# motorEncoder.net
KiCad netlist of a schematic drawn in Altium Designer
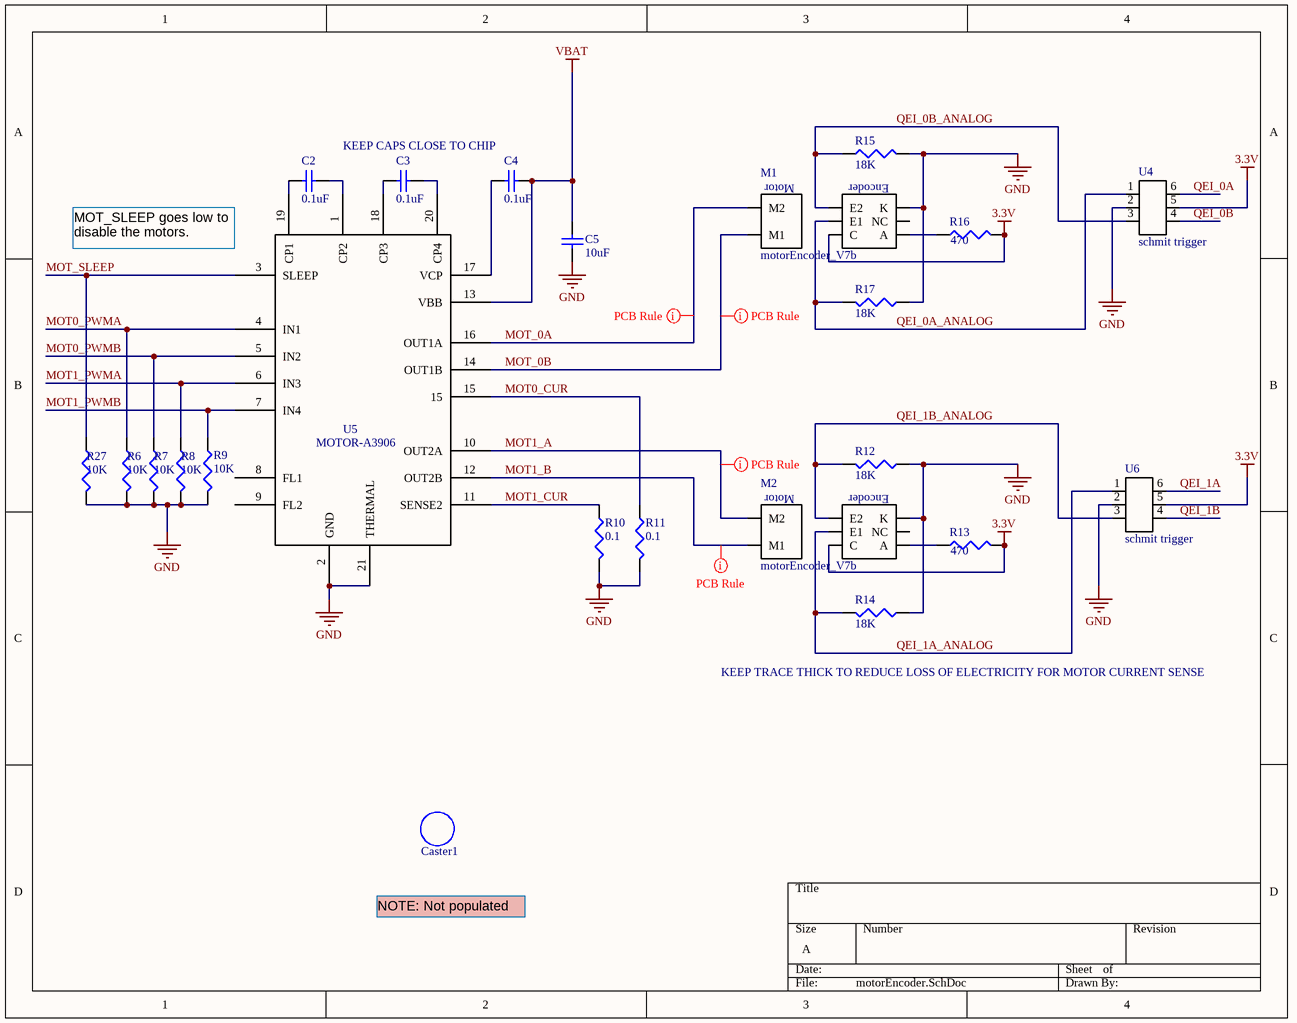
[diagram p0: motorEncoder.SchDoc]

(export (version "E")
  (design (tool "Eeschema 10.0.6"))
  (components
    (comp (ref "C2")
      (value "0.1uF")
      (footprint "CAPC1005L")
      (description "Capacitor (Semiconductor SIM Model)")
      (fields (field (name "Comment") "Cap Semi") (field (name "PUBLISHER") "Altium Limited"))
      (libsource (lib "Miscellaneous Devices") (part "Cap Semi"))
    )
    (comp (ref "C3")
      (value "0.1uF")
      (footprint "CAPC1005L")
      (description "Capacitor (Semiconductor SIM Model)")
      (fields (field (name "Comment") "Cap Semi") (field (name "PUBLISHER") "Altium Limited"))
      (libsource (lib "Miscellaneous Devices") (part "Cap Semi"))
    )
    (comp (ref "C4")
      (value "0.1uF")
      (footprint "CAPC1005L")
      (description "Capacitor (Semiconductor SIM Model)")
      (fields (field (name "Comment") "Cap Semi") (field (name "PUBLISHER") "Altium Limited"))
      (libsource (lib "Miscellaneous Devices") (part "Cap Semi"))
    )
    (comp (ref "C5")
      (value "10uF")
      (footprint "CAPC1608L")
      (description "Capacitor (Semiconductor SIM Model)")
      (fields (field (name "Comment") "Cap Semi") (field (name "PUBLISHER") "Altium Limited"))
      (libsource (lib "Miscellaneous Devices") (part "Cap Semi"))
    )
    (comp (ref "Caster1")
      (value "non connect")
      (footprint "3/4\"CASTER2")
      (description "This is just a space saver to get the caster onto the pcb")
      (libsource (lib "mrone") (part "Caster 3/4in"))
    )
    (comp (ref "M1")
      (value "motorEncoder_V7b")
      (footprint "motorEncoder_V7b")
      (libsource (lib "mrone") (part "motorEncoder_V7b"))
    )
    (comp (ref "M2")
      (value "motorEncoder_V7b")
      (footprint "motorEncoder_V7b")
      (libsource (lib "mrone") (part "motorEncoder_V7b"))
    )
    (comp (ref "R6")
      (value "10K")
      (footprint "RESC1608L")
      (description "Resistor")
      (fields (field (name "Comment") "Res3") (field (name "PUBLISHER") "Altium Limited"))
      (libsource (lib "Miscellaneous Devices") (part "Res3"))
    )
    (comp (ref "R7")
      (value "10K")
      (footprint "RESC1608L")
      (description "Resistor")
      (fields (field (name "Comment") "Res3") (field (name "PUBLISHER") "Altium Limited"))
      (libsource (lib "Miscellaneous Devices") (part "Res3"))
    )
    (comp (ref "R8")
      (value "10K")
      (footprint "RESC1608L")
      (description "Resistor")
      (fields (field (name "Comment") "Res3") (field (name "PUBLISHER") "Altium Limited"))
      (libsource (lib "Miscellaneous Devices") (part "Res3"))
    )
    (comp (ref "R9")
      (value "10K")
      (footprint "RESC1608L")
      (description "Resistor")
      (fields (field (name "Comment") "Res3") (field (name "PUBLISHER") "Altium Limited"))
      (libsource (lib "Miscellaneous Devices") (part "Res3"))
    )
    (comp (ref "R10")
      (value "0.1")
      (footprint "RESC1608L")
      (description "Resistor")
      (fields (field (name "Comment") "Res3") (field (name "PUBLISHER") "Altium Limited"))
      (libsource (lib "Miscellaneous Devices") (part "Res3"))
    )
    (comp (ref "R11")
      (value "0.1")
      (footprint "RESC1608L")
      (description "Resistor")
      (fields (field (name "Comment") "Res3") (field (name "PUBLISHER") "Altium Limited"))
      (libsource (lib "Miscellaneous Devices") (part "Res3"))
    )
    (comp (ref "R12")
      (value "18K")
      (footprint "RESC1608L")
      (description "Resistor")
      (fields (field (name "PUBLISHER") "Altium Limited"))
      (libsource (lib "Miscellaneous Devices") (part "Res3"))
    )
    (comp (ref "R13")
      (value "470")
      (footprint "RESC1608L")
      (description "Resistor")
      (fields (field (name "PUBLISHER") "Altium Limited"))
      (libsource (lib "Miscellaneous Devices") (part "Res3"))
    )
    (comp (ref "R14")
      (value "18K")
      (footprint "RESC1608L")
      (description "Resistor")
      (fields (field (name "PUBLISHER") "Altium Limited"))
      (libsource (lib "Miscellaneous Devices") (part "Res3"))
    )
    (comp (ref "R15")
      (value "18K")
      (footprint "RESC1608L")
      (description "Resistor")
      (fields (field (name "PUBLISHER") "Altium Limited"))
      (libsource (lib "Miscellaneous Devices") (part "Res3"))
    )
    (comp (ref "R16")
      (value "470")
      (footprint "RESC1608L")
      (description "Resistor")
      (fields (field (name "PUBLISHER") "Altium Limited"))
      (libsource (lib "Miscellaneous Devices") (part "Res3"))
    )
    (comp (ref "R17")
      (value "18K")
      (footprint "RESC1608L")
      (description "Resistor")
      (fields (field (name "PUBLISHER") "Altium Limited"))
      (libsource (lib "Miscellaneous Devices") (part "Res3"))
    )
    (comp (ref "R27")
      (value "10K")
      (footprint "CAPC1608L")
      (description "Resistor")
      (fields (field (name "Comment") "Res3") (field (name "PUBLISHER") "Altium Limited"))
      (libsource (lib "Miscellaneous Devices") (part "Res3"))
    )
    (comp (ref "U4")
      (value "schmit trigger")
      (footprint "DCK(R-PDSO-C6)")
      (libsource (lib "mrone") (part "schmit trigger"))
    )
    (comp (ref "U5")
      (value "MOTOR-A3906")
      (footprint "QFN-20")
      (libsource (lib "V2_altium") (part "MOTOR-A3906"))
    )
    (comp (ref "U6")
      (value "schmit trigger")
      (footprint "DCK(R-PDSO-C6)")
      (libsource (lib "mrone") (part "schmit trigger"))
    )
  )
  (nets
    (net (code "2") (name "/MOT0_CUR") (class "Default")
      (node (ref "R11") (pin "1") (pinfunction "1_1") (pintype "passive"))
      (node (ref "U5") (pin "15") (pinfunction "15_15") (pintype "passive"))
    )
    (net (code "3") (name "/MOT0_PWMA") (class "Default")
      (node (ref "R6") (pin "1") (pinfunction "1_1") (pintype "passive"))
      (node (ref "U5") (pin "4") (pinfunction "IN1_4") (pintype "passive"))
    )
    (net (code "4") (name "/MOT0_PWMB") (class "Default")
      (node (ref "R7") (pin "1") (pinfunction "1_1") (pintype "passive"))
      (node (ref "U5") (pin "5") (pinfunction "IN2_5") (pintype "passive"))
    )
    (net (code "5") (name "/MOT1_A") (class "Default")
      (node (ref "M2") (pin "M2") (pinfunction "M2_M2") (pintype "passive"))
      (node (ref "U5") (pin "10") (pinfunction "OUT2A_10") (pintype "passive"))
    )
    (net (code "6") (name "/MOT1_B") (class "Default")
      (node (ref "M2") (pin "M1") (pinfunction "M1_M1") (pintype "passive"))
      (node (ref "U5") (pin "12") (pinfunction "OUT2B_12") (pintype "passive"))
    )
    (net (code "7") (name "/MOT1_CUR") (class "Default")
      (node (ref "R10") (pin "1") (pinfunction "1_1") (pintype "passive"))
      (node (ref "U5") (pin "11") (pinfunction "SENSE2_11") (pintype "passive"))
    )
    (net (code "8") (name "/MOT1_PWMA") (class "Default")
      (node (ref "R8") (pin "1") (pinfunction "1_1") (pintype "passive"))
      (node (ref "U5") (pin "6") (pinfunction "IN3_6") (pintype "passive"))
    )
    (net (code "9") (name "/MOT1_PWMB") (class "Default")
      (node (ref "R9") (pin "1") (pinfunction "1_1") (pintype "passive"))
      (node (ref "U5") (pin "7") (pinfunction "IN4_7") (pintype "passive"))
    )
    (net (code "10") (name "/MOT_0A") (class "Default")
      (node (ref "M1") (pin "M2") (pinfunction "M2_M2") (pintype "passive"))
      (node (ref "U5") (pin "16") (pinfunction "OUT1A_16") (pintype "passive"))
    )
    (net (code "11") (name "/MOT_0B") (class "Default")
      (node (ref "M1") (pin "M1") (pinfunction "M1_M1") (pintype "passive"))
      (node (ref "U5") (pin "14") (pinfunction "OUT1B_14") (pintype "passive"))
    )
    (net (code "12") (name "/MOT_SLEEP") (class "Default")
      (node (ref "R27") (pin "1") (pinfunction "1_1") (pintype "passive"))
      (node (ref "U5") (pin "3") (pinfunction "SLEEP_3") (pintype "passive"))
    )
    (net (code "13") (name "/QEI_0A") (class "Default")
      (node (ref "U4") (pin "6") (pinfunction "4_6") (pintype "passive"))
    )
    (net (code "14") (name "/QEI_0A_ANALOG") (class "Default")
      (node (ref "M1") (pin "E1") (pinfunction "E1_E1") (pintype "passive"))
      (node (ref "R17") (pin "2") (pinfunction "2_2") (pintype "passive"))
      (node (ref "U4") (pin "1") (pinfunction "1_1") (pintype "passive"))
    )
    (net (code "15") (name "/QEI_0B") (class "Default")
      (node (ref "U4") (pin "4") (pinfunction "4_4") (pintype "passive"))
    )
    (net (code "16") (name "/QEI_0B_ANALOG") (class "Default")
      (node (ref "M1") (pin "E2") (pinfunction "E2_E2") (pintype "passive"))
      (node (ref "R15") (pin "1") (pinfunction "1_1") (pintype "passive"))
      (node (ref "U4") (pin "3") (pinfunction "3_3") (pintype "passive"))
    )
    (net (code "17") (name "/QEI_1A") (class "Default")
      (node (ref "U6") (pin "6") (pinfunction "4_6") (pintype "passive"))
    )
    (net (code "18") (name "/QEI_1A_ANALOG") (class "Default")
      (node (ref "M2") (pin "E1") (pinfunction "E1_E1") (pintype "passive"))
      (node (ref "R14") (pin "2") (pinfunction "2_2") (pintype "passive"))
      (node (ref "U6") (pin "1") (pinfunction "1_1") (pintype "passive"))
    )
    (net (code "19") (name "/QEI_1B") (class "Default")
      (node (ref "U6") (pin "4") (pinfunction "4_4") (pintype "passive"))
    )
    (net (code "20") (name "/QEI_1B_ANALOG") (class "Default")
      (node (ref "M2") (pin "E2") (pinfunction "E2_E2") (pintype "passive"))
      (node (ref "R12") (pin "2") (pinfunction "2_2") (pintype "passive"))
      (node (ref "U6") (pin "3") (pinfunction "3_3") (pintype "passive"))
    )
    (net (code "21") (name "3.3V") (class "Default")
      (node (ref "M1") (pin "C") (pinfunction "C_C") (pintype "passive"))
      (node (ref "M2") (pin "C") (pinfunction "C_C") (pintype "passive"))
      (node (ref "R13") (pin "2") (pinfunction "2_2") (pintype "passive"))
      (node (ref "R16") (pin "2") (pinfunction "2_2") (pintype "passive"))
      (node (ref "U4") (pin "5") (pinfunction "5_5") (pintype "passive"))
      (node (ref "U6") (pin "5") (pinfunction "5_5") (pintype "passive"))
    )
    (net (code "22") (name "GND") (class "Default")
      (node (ref "C5") (pin "1") (pinfunction "1_1") (pintype "passive"))
      (node (ref "M1") (pin "K") (pinfunction "K_K") (pintype "passive"))
      (node (ref "M2") (pin "K") (pinfunction "K_K") (pintype "passive"))
      (node (ref "R10") (pin "2") (pinfunction "2_2") (pintype "passive"))
      (node (ref "R11") (pin "2") (pinfunction "2_2") (pintype "passive"))
      (node (ref "R12") (pin "1") (pinfunction "1_1") (pintype "passive"))
      (node (ref "R14") (pin "1") (pinfunction "1_1") (pintype "passive"))
      (node (ref "R15") (pin "2") (pinfunction "2_2") (pintype "passive"))
      (node (ref "R17") (pin "1") (pinfunction "1_1") (pintype "passive"))
      (node (ref "R27") (pin "2") (pinfunction "2_2") (pintype "passive"))
      (node (ref "R6") (pin "2") (pinfunction "2_2") (pintype "passive"))
      (node (ref "R7") (pin "2") (pinfunction "2_2") (pintype "passive"))
      (node (ref "R8") (pin "2") (pinfunction "2_2") (pintype "passive"))
      (node (ref "R9") (pin "2") (pinfunction "2_2") (pintype "passive"))
      (node (ref "U4") (pin "2") (pinfunction "2_2") (pintype "passive"))
      (node (ref "U5") (pin "2") (pinfunction "GND_2") (pintype "passive"))
      (node (ref "U5") (pin "21") (pinfunction "THERMAL_21") (pintype "passive"))
      (node (ref "U6") (pin "2") (pinfunction "2_2") (pintype "passive"))
    )
    (net (code "23") (name "Net-(M1-PadA)") (class "Default")
      (node (ref "M1") (pin "A") (pinfunction "A_A") (pintype "passive"))
      (node (ref "R16") (pin "1") (pinfunction "1_1") (pintype "passive"))
    )
    (net (code "24") (name "Net-(M2-PadA)") (class "Default")
      (node (ref "M2") (pin "A") (pinfunction "A_A") (pintype "passive"))
      (node (ref "R13") (pin "1") (pinfunction "1_1") (pintype "passive"))
    )
    (net (code "25") (name "Net-(U5-CP1)") (class "Default")
      (node (ref "C2") (pin "1") (pinfunction "1_1") (pintype "passive"))
      (node (ref "U5") (pin "19") (pinfunction "CP1_19") (pintype "passive"))
    )
    (net (code "26") (name "Net-(U5-CP2)") (class "Default")
      (node (ref "C2") (pin "2") (pinfunction "2_2") (pintype "passive"))
      (node (ref "U5") (pin "1") (pinfunction "CP2_1") (pintype "passive"))
    )
    (net (code "27") (name "Net-(U5-CP3)") (class "Default")
      (node (ref "C3") (pin "1") (pinfunction "1_1") (pintype "passive"))
      (node (ref "U5") (pin "18") (pinfunction "CP3_18") (pintype "passive"))
    )
    (net (code "28") (name "Net-(U5-CP4)") (class "Default")
      (node (ref "C3") (pin "2") (pinfunction "2_2") (pintype "passive"))
      (node (ref "U5") (pin "20") (pinfunction "CP4_20") (pintype "passive"))
    )
    (net (code "29") (name "Net-(U5-VCP)") (class "Default")
      (node (ref "C4") (pin "2") (pinfunction "2_2") (pintype "passive"))
      (node (ref "U5") (pin "17") (pinfunction "VCP_17") (pintype "passive"))
    )
    (net (code "30") (name "VBAT") (class "Default")
      (node (ref "C4") (pin "1") (pinfunction "1_1") (pintype "passive"))
      (node (ref "C5") (pin "2") (pinfunction "2_2") (pintype "passive"))
      (node (ref "U5") (pin "13") (pinfunction "VBB_13") (pintype "passive"))
    )
    (net (code "31") (name "unconnected-(M1-PadNC)") (class "Default")
      (node (ref "M1") (pin "NC") (pinfunction "NC_NC") (pintype "passive"))
    )
    (net (code "32") (name "unconnected-(M2-PadNC)") (class "Default")
      (node (ref "M2") (pin "NC") (pinfunction "NC_NC") (pintype "passive"))
    )
    (net (code "33") (name "unconnected-(U5-FL1-Pad8)") (class "Default")
      (node (ref "U5") (pin "8") (pinfunction "FL1_8") (pintype "passive"))
    )
    (net (code "34") (name "unconnected-(U5-FL2-Pad9)") (class "Default")
      (node (ref "U5") (pin "9") (pinfunction "FL2_9") (pintype "passive"))
    )
  )
)
